# Grove_-_12-bit_Magnetic_Rotary_Position_.net
KiCad netlist of a schematic drawn in EAGLE
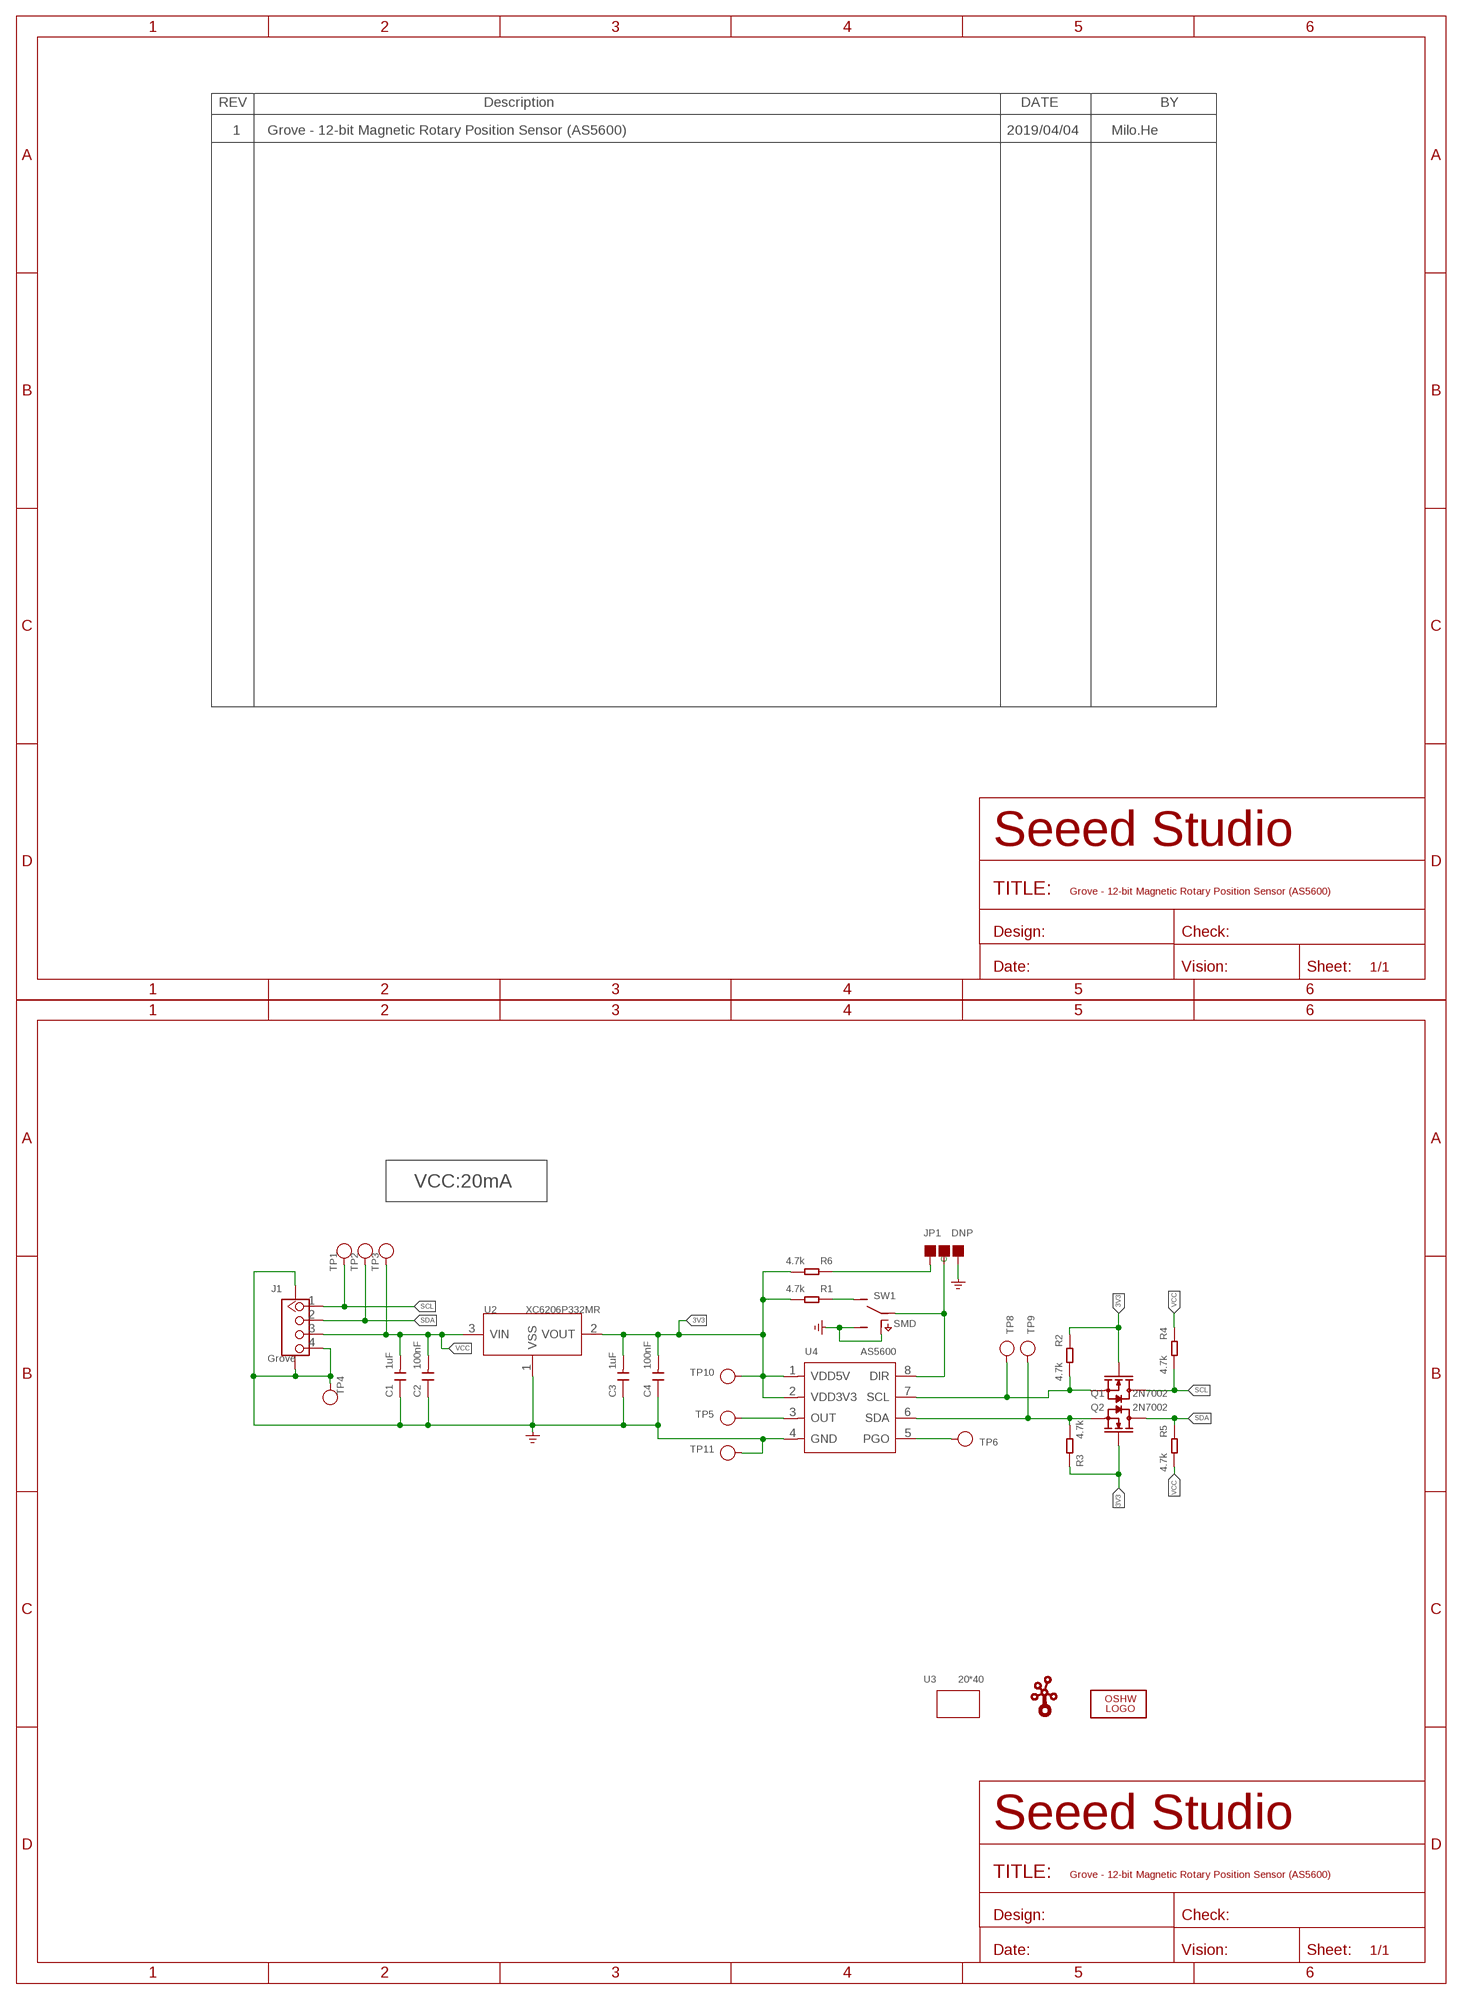
[diagram p0: schematic, sheet 1]

(export (version "E")
  (design (tool "Eeschema 10.0.6"))
  (components
    (comp (ref "C1")
      (value "1uF")
      (footprint "eagle-import:C0402")
      (libsource (lib "eagle-import") (part "CAP-0402"))
    )
    (comp (ref "C2")
      (value "100nF")
      (footprint "eagle-import:C0402")
      (libsource (lib "eagle-import") (part "CAP-0402"))
    )
    (comp (ref "C3")
      (value "1uF")
      (footprint "eagle-import:C0402")
      (libsource (lib "eagle-import") (part "CAP-0402"))
    )
    (comp (ref "C4")
      (value "100nF")
      (footprint "eagle-import:C0402")
      (libsource (lib "eagle-import") (part "CAP-0402"))
    )
    (comp (ref "J1")
      (value "Grove")
      (footprint "eagle-import:HW4-SMD-2.0-90D")
      (libsource (lib "eagle-import") (part "GROVE-CONNECTOR-SMD-320110032"))
    )
    (comp (ref "JP1")
      (value "DNP")
      (footprint "eagle-import:3P-SMD")
      (libsource (lib "eagle-import") (part "JP-3P"))
    )
    (comp (ref "LOGO1")
      (value "LOGO-OSHW-FILLX0150-NT")
      (footprint "eagle-import:OSHW_FILLX150_NOTEXT")
      (fields (field (name "PARTNO") "DNP"))
      (libsource (lib "eagle-import") (part "LOGO-OSHW-FILLX0150-NT"))
    )
    (comp (ref "Q1")
      (value "2N7002")
      (footprint "eagle-import:SOT-323")
      (libsource (lib "eagle-import") (part "MOSFET-N'SI1304BDL'"))
    )
    (comp (ref "Q2")
      (value "2N7002")
      (footprint "eagle-import:SOT-323")
      (libsource (lib "eagle-import") (part "MOSFET-N'SI1304BDL'"))
    )
    (comp (ref "R1")
      (value "4.7k")
      (footprint "eagle-import:R0402")
      (libsource (lib "eagle-import") (part "RES-0402"))
    )
    (comp (ref "R2")
      (value "4.7k")
      (footprint "eagle-import:R0402")
      (libsource (lib "eagle-import") (part "RES-0402"))
    )
    (comp (ref "R3")
      (value "4.7k")
      (footprint "eagle-import:R0402")
      (libsource (lib "eagle-import") (part "RES-0402"))
    )
    (comp (ref "R4")
      (value "4.7k")
      (footprint "eagle-import:R0402")
      (libsource (lib "eagle-import") (part "RES-0402"))
    )
    (comp (ref "R5")
      (value "4.7k")
      (footprint "eagle-import:R0402")
      (libsource (lib "eagle-import") (part "RES-0402"))
    )
    (comp (ref "R6")
      (value "4.7k")
      (footprint "eagle-import:R0402")
      (libsource (lib "eagle-import") (part "RES-0402"))
    )
    (comp (ref "SW1")
      (value "SMD")
      (footprint "eagle-import:SW7-SMD-L6.7X2.7X3.2MM")
      (libsource (lib "eagle-import") (part "SWITCH-3+4P-311030001"))
    )
    (comp (ref "TP1")
      (value "Test")
      (footprint "eagle-import:TP-D45MIL")
      (fields (field (name "PARTNO") "DNP"))
      (libsource (lib "eagle-import") (part "TEST-POINT'4545'"))
    )
    (comp (ref "TP2")
      (value "Test")
      (footprint "eagle-import:TP-D45MIL")
      (fields (field (name "PARTNO") "DNP"))
      (libsource (lib "eagle-import") (part "TEST-POINT'4545'"))
    )
    (comp (ref "TP3")
      (value "Test")
      (footprint "eagle-import:TP-D45MIL")
      (fields (field (name "PARTNO") "DNP"))
      (libsource (lib "eagle-import") (part "TEST-POINT'4545'"))
    )
    (comp (ref "TP4")
      (value "Test")
      (footprint "eagle-import:TP-D45MIL")
      (fields (field (name "PARTNO") "DNP"))
      (libsource (lib "eagle-import") (part "TEST-POINT'4545'"))
    )
    (comp (ref "TP5")
      (value "Test")
      (footprint "eagle-import:TP-80X40MIL")
      (libsource (lib "eagle-import") (part "TEST-POINT'4080'"))
    )
    (comp (ref "TP6")
      (value "Test")
      (footprint "eagle-import:TP-80X40MIL")
      (libsource (lib "eagle-import") (part "TEST-POINT'4080'"))
    )
    (comp (ref "TP8")
      (value "Test")
      (footprint "eagle-import:TP-80X40MIL")
      (libsource (lib "eagle-import") (part "TEST-POINT'4080'"))
    )
    (comp (ref "TP9")
      (value "Test")
      (footprint "eagle-import:TP-80X40MIL")
      (libsource (lib "eagle-import") (part "TEST-POINT'4080'"))
    )
    (comp (ref "TP10")
      (value "Test")
      (footprint "eagle-import:TP-80X40MIL")
      (libsource (lib "eagle-import") (part "TEST-POINT'4080'"))
    )
    (comp (ref "TP11")
      (value "Test")
      (footprint "eagle-import:TP-80X40MIL")
      (libsource (lib "eagle-import") (part "TEST-POINT'4080'"))
    )
    (comp (ref "U$4")
      (value "LOGO-GROVETWIGLOGO_SMALL")
      (footprint "eagle-import:GROVE-SILK-SMALL")
      (fields (field (name "PARTNO") "DNP"))
      (libsource (lib "eagle-import") (part "LOGO-GROVETWIGLOGO_SMALL"))
    )
    (comp (ref "U2")
      (value "XC6206P332MR")
      (footprint "eagle-import:SOT-23")
      (libsource (lib "eagle-import") (part "PMIC-XC6206PMR"))
    )
    (comp (ref "U3")
      (value "20*40")
      (footprint "eagle-import:GROVE-1_2-TEST-PLATFORM-TOP")
      (libsource (lib "eagle-import") (part "GROVE-1X2-TOP"))
    )
    (comp (ref "U4")
      (value "AS5600")
      (footprint "eagle-import:SOIC8-1.27-5X4MM")
      (libsource (lib "eagle-import") (part "SENSOR-AS5600"))
    )
  )
  (nets
    (net (code "1") (name "3V3") (class "Default")
      (node (ref "C3") (pin "2") (pinfunction "2_2") (pintype "passive"))
      (node (ref "C4") (pin "2") (pinfunction "2_2") (pintype "passive"))
      (node (ref "Q1") (pin "1") (pinfunction "G_1") (pintype "passive"))
      (node (ref "Q2") (pin "1") (pinfunction "G_1") (pintype "passive"))
      (node (ref "R1") (pin "2") (pinfunction "2_2") (pintype "passive"))
      (node (ref "R2") (pin "1") (pinfunction "1_1") (pintype "passive"))
      (node (ref "R3") (pin "1") (pinfunction "1_1") (pintype "passive"))
      (node (ref "R6") (pin "2") (pinfunction "2_2") (pintype "passive"))
      (node (ref "TP10") (pin "1") (pinfunction "T_1") (pintype "bidirectional"))
      (node (ref "U2") (pin "2") (pinfunction "VOUT_2") (pintype "bidirectional"))
      (node (ref "U4") (pin "1") (pinfunction "VDD5V_1") (pintype "bidirectional"))
      (node (ref "U4") (pin "2") (pinfunction "VDD3V3_2") (pintype "bidirectional"))
    )
    (net (code "2") (name "GND_POWER") (class "Default")
      (node (ref "C1") (pin "1") (pinfunction "1_1") (pintype "passive"))
      (node (ref "C2") (pin "1") (pinfunction "1_1") (pintype "passive"))
      (node (ref "C3") (pin "1") (pinfunction "1_1") (pintype "passive"))
      (node (ref "C4") (pin "1") (pinfunction "1_1") (pintype "passive"))
      (node (ref "J1") (pin "4") (pinfunction "4_4") (pintype "bidirectional"))
      (node (ref "J1") (pin "SS1") (pinfunction "SS1_SS1") (pintype "bidirectional"))
      (node (ref "J1") (pin "SS2") (pinfunction "SS2_SS2") (pintype "bidirectional"))
      (node (ref "JP1") (pin "00") (pinfunction "R_00") (pintype "bidirectional"))
      (node (ref "SW1") (pin "3") (pinfunction "B_3") (pintype "bidirectional"))
      (node (ref "SW1") (pin "SS1") (pinfunction "SS2_SS1") (pintype "bidirectional"))
      (node (ref "SW1") (pin "SS2") (pinfunction "SS2_SS2") (pintype "bidirectional"))
      (node (ref "SW1") (pin "SS3") (pinfunction "SS2_SS3") (pintype "bidirectional"))
      (node (ref "SW1") (pin "SS4") (pinfunction "SS2_SS4") (pintype "bidirectional"))
      (node (ref "TP11") (pin "1") (pinfunction "T_1") (pintype "bidirectional"))
      (node (ref "TP4") (pin "T") (pinfunction "T_T") (pintype "bidirectional"))
      (node (ref "U2") (pin "1") (pinfunction "VSS_1") (pintype "bidirectional"))
      (node (ref "U4") (pin "4") (pinfunction "GND_4") (pintype "bidirectional"))
    )
    (net (code "3") (name "Net-(JP1-C)") (class "Default")
      (node (ref "JP1") (pin "MM") (pinfunction "C_MM") (pintype "bidirectional"))
      (node (ref "SW1") (pin "2") (pinfunction "COM_2") (pintype "bidirectional"))
      (node (ref "U4") (pin "8") (pinfunction "DIR_8") (pintype "bidirectional"))
    )
    (net (code "4") (name "Net-(JP1-L)") (class "Default")
      (node (ref "JP1") (pin "11") (pinfunction "L_11") (pintype "bidirectional"))
      (node (ref "R6") (pin "1") (pinfunction "1_1") (pintype "passive"))
    )
    (net (code "5") (name "Net-(Q1-S)") (class "Default")
      (node (ref "Q1") (pin "2") (pinfunction "S_2") (pintype "passive"))
      (node (ref "R2") (pin "2") (pinfunction "2_2") (pintype "passive"))
      (node (ref "TP8") (pin "1") (pinfunction "T_1") (pintype "bidirectional"))
      (node (ref "U4") (pin "7") (pinfunction "SCL_7") (pintype "bidirectional"))
    )
    (net (code "6") (name "Net-(Q2-S)") (class "Default")
      (node (ref "Q2") (pin "2") (pinfunction "S_2") (pintype "passive"))
      (node (ref "R3") (pin "2") (pinfunction "2_2") (pintype "passive"))
      (node (ref "TP9") (pin "1") (pinfunction "T_1") (pintype "bidirectional"))
      (node (ref "U4") (pin "6") (pinfunction "SDA_6") (pintype "bidirectional"))
    )
    (net (code "7") (name "Net-(SW1-A)") (class "Default")
      (node (ref "R1") (pin "1") (pinfunction "1_1") (pintype "passive"))
      (node (ref "SW1") (pin "1") (pinfunction "A_1") (pintype "bidirectional"))
    )
    (net (code "8") (name "Net-(TP5-T)") (class "Default")
      (node (ref "TP5") (pin "1") (pinfunction "T_1") (pintype "bidirectional"))
      (node (ref "U4") (pin "3") (pinfunction "OUT_3") (pintype "bidirectional"))
    )
    (net (code "9") (name "Net-(TP6-T)") (class "Default")
      (node (ref "TP6") (pin "1") (pinfunction "T_1") (pintype "bidirectional"))
      (node (ref "U4") (pin "5") (pinfunction "PGO_5") (pintype "bidirectional"))
    )
    (net (code "10") (name "SCL") (class "Default")
      (node (ref "J1") (pin "1") (pinfunction "1_1") (pintype "bidirectional"))
      (node (ref "Q1") (pin "3") (pinfunction "D_3") (pintype "passive"))
      (node (ref "R4") (pin "2") (pinfunction "2_2") (pintype "passive"))
      (node (ref "TP1") (pin "T") (pinfunction "T_T") (pintype "bidirectional"))
    )
    (net (code "11") (name "SDA") (class "Default")
      (node (ref "J1") (pin "2") (pinfunction "2_2") (pintype "bidirectional"))
      (node (ref "Q2") (pin "3") (pinfunction "D_3") (pintype "passive"))
      (node (ref "R5") (pin "1") (pinfunction "1_1") (pintype "passive"))
      (node (ref "TP2") (pin "T") (pinfunction "T_T") (pintype "bidirectional"))
    )
    (net (code "12") (name "VCC") (class "Default")
      (node (ref "C1") (pin "2") (pinfunction "2_2") (pintype "passive"))
      (node (ref "C2") (pin "2") (pinfunction "2_2") (pintype "passive"))
      (node (ref "J1") (pin "3") (pinfunction "3_3") (pintype "bidirectional"))
      (node (ref "R4") (pin "1") (pinfunction "1_1") (pintype "passive"))
      (node (ref "R5") (pin "2") (pinfunction "2_2") (pintype "passive"))
      (node (ref "TP3") (pin "T") (pinfunction "T_T") (pintype "bidirectional"))
      (node (ref "U2") (pin "3") (pinfunction "VIN_3") (pintype "bidirectional"))
    )
  )
)
